# RAFT_DuckLink_UART_Bridge.net
KiCad netlist of a schematic drawn in EAGLE
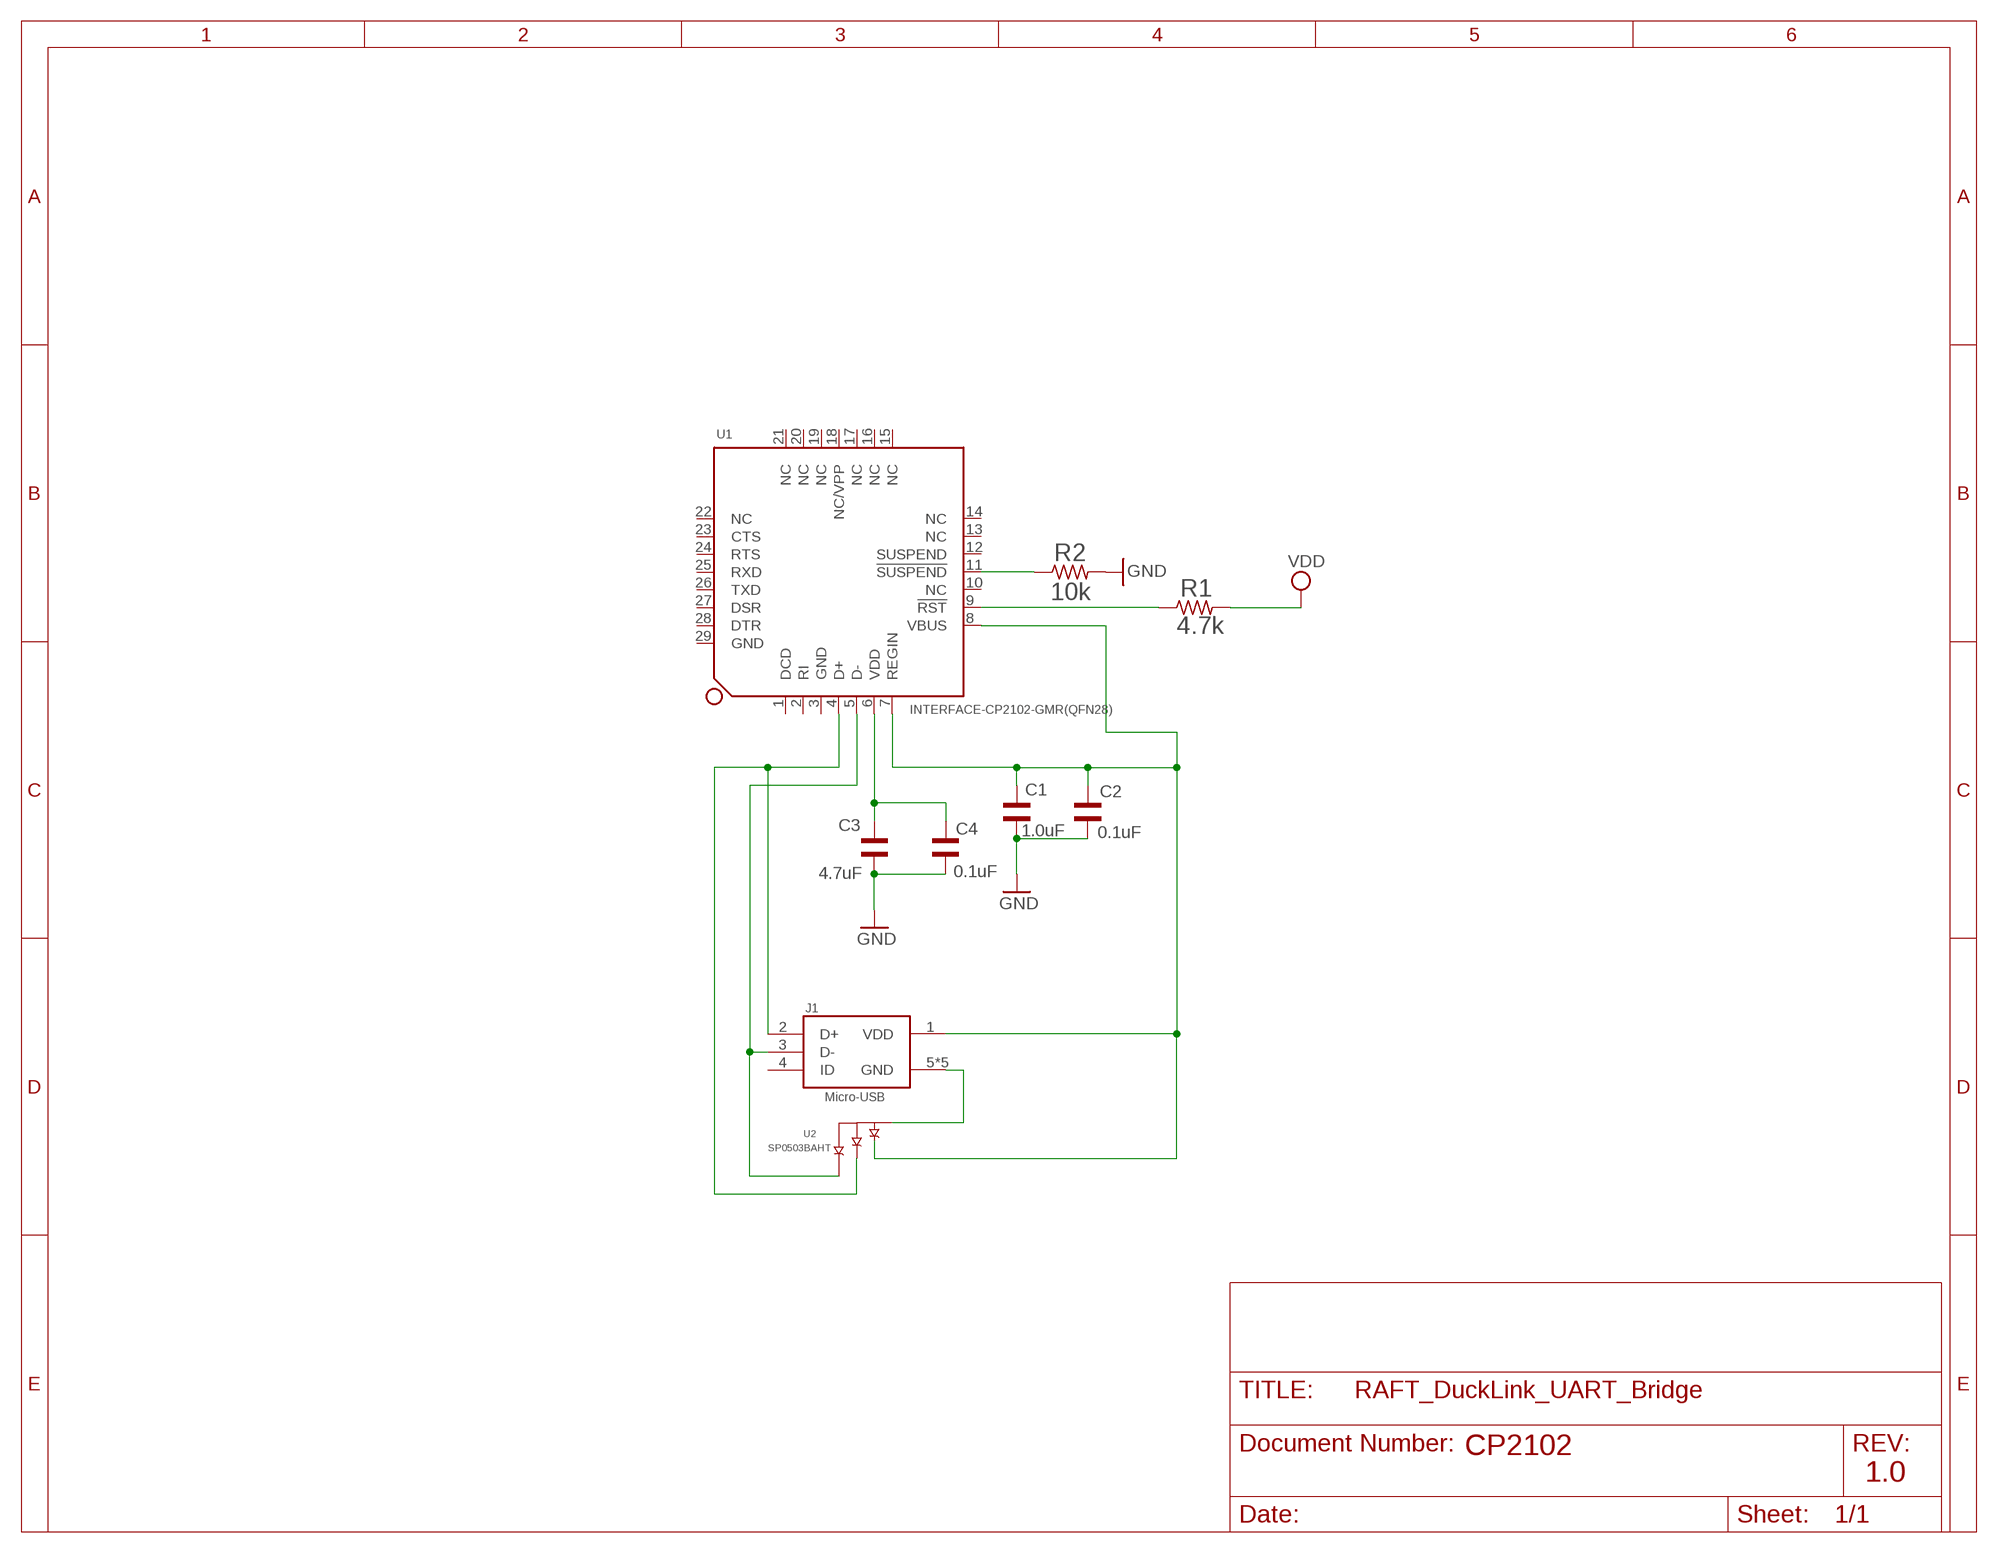
[diagram p0: schematic, sheet 1]

(export (version "E")
  (design (tool "Eeschema 10.0.6"))
  (components
    (comp (ref "C1")
      (value "1.0uF")
      (footprint "eagle-import:CAPC1005X70N")
      (fields (field (name "MF") "Murata") (field (name "MP") "GCM155C71A105KE38D"))
      (libsource (lib "eagle-import") (part "GCM155C71A105KE38D"))
    )
    (comp (ref "C2")
      (value "0.1uF")
      (footprint "eagle-import:CAPC1005X55N")
      (fields (field (name "MF") "Murata") (field (name "MP") "GRM155R71C104KA88D"))
      (libsource (lib "eagle-import") (part "GRM155R71C104KA88D"))
    )
    (comp (ref "C3")
      (value "4.7uF")
      (footprint "eagle-import:CAPC1005X55N")
      (fields (field (name "MF") "Murata") (field (name "MP") "GRM155R60J475ME87D"))
      (libsource (lib "eagle-import") (part "GRM155R60J475ME87D"))
    )
    (comp (ref "C4")
      (value "0.1uF")
      (footprint "eagle-import:CAPC1005X55N")
      (fields (field (name "MF") "Murata") (field (name "MP") "GRM155R71C104KA88D"))
      (libsource (lib "eagle-import") (part "GRM155R71C104KA88D"))
    )
    (comp (ref "J1")
      (value "Micro-USB")
      (footprint "eagle-import:MOLEX_105017-0001")
      (fields
        (field (name "DIGI-KEY_PART_NUMBER") "WM1399CT-ND")
        (field (name "MF") "Molex")
        (field (name "MP") "1050170001")
      )
      (libsource (lib "eagle-import") (part "105017-0001FIXED"))
    )
    (comp (ref "R1")
      (value "4.7k")
      (footprint "eagle-import:RESC1005X35N")
      (fields
        (field (name "DIGI-KEY_PART_NUMBER") "541-3974-1-ND")
        (field (name "MF") "Vishay")
        (field (name "MP") "CRCW04024K70JNEDC")
      )
      (libsource (lib "eagle-import") (part "CRCW04024K70JNEDC"))
    )
    (comp (ref "R2")
      (value "10k")
      (footprint "eagle-import:RESC1005X40N")
      (fields
        (field (name "DIGI-KEY_PART_NUMBER") "541-10KJCT-ND")
        (field (name "MF") "Vishay Dale")
        (field (name "MP") "CRCW040210K0JNED")
      )
      (libsource (lib "eagle-import") (part "CRCW040210K0JNED"))
    )
    (comp (ref "U1")
      (value "INTERFACE-CP2102-GMR(QFN28)")
      (footprint "eagle-import:QFN28G_0.5-5X5MM")
      (fields (field (name "MF") "Silicon") (field (name "MP") "CP2102-GMR"))
      (libsource (lib "eagle-import") (part "INTERFACE-CP2102-GMR(QFN28)"))
    )
    (comp (ref "U2")
      (value "SP0503BAHT")
      (footprint "eagle-import:SOT143")
      (fields (field (name "DIGI-KEY_PART_NUMBER") "SP0503BAHT-ND") (field (name "MF") "Littelfuse Inc."))
      (libsource (lib "eagle-import") (part "SP0503BAHT"))
    )
  )
  (nets
    (net (code "1") (name "GND") (class "Default")
      (node (ref "C1") (pin "1") (pinfunction "1_1") (pintype "passive"))
      (node (ref "C2") (pin "1") (pinfunction "1_1") (pintype "passive"))
      (node (ref "C3") (pin "1") (pinfunction "1_1") (pintype "passive"))
      (node (ref "C4") (pin "1") (pinfunction "1_1") (pintype "passive"))
      (node (ref "R2") (pin "2") (pinfunction "2_2") (pintype "passive"))
    )
    (net (code "2") (name "Net-(J1-D+)") (class "Default")
      (node (ref "J1") (pin "2") (pinfunction "D+_2") (pintype "bidirectional"))
      (node (ref "U1") (pin "4") (pinfunction "D+_4") (pintype "bidirectional"))
      (node (ref "U2") (pin "3") (pinfunction "B_3") (pintype "bidirectional"))
    )
    (net (code "3") (name "Net-(J1-D-)") (class "Default")
      (node (ref "J1") (pin "3") (pinfunction "D-_3") (pintype "bidirectional"))
      (node (ref "U1") (pin "5") (pinfunction "D-_5") (pintype "bidirectional"))
      (node (ref "U2") (pin "4") (pinfunction "C_4") (pintype "bidirectional"))
    )
    (net (code "4") (name "Net-(J1-VDD)") (class "Default")
      (node (ref "C1") (pin "2") (pinfunction "2_2") (pintype "passive"))
      (node (ref "C2") (pin "2") (pinfunction "2_2") (pintype "passive"))
      (node (ref "J1") (pin "1") (pinfunction "VDD_1") (pintype "power_in"))
      (node (ref "U1") (pin "7") (pinfunction "REGIN_7") (pintype "bidirectional"))
      (node (ref "U1") (pin "8") (pinfunction "VBUS_8") (pintype "bidirectional"))
      (node (ref "U2") (pin "2") (pinfunction "A_2") (pintype "bidirectional"))
    )
    (net (code "5") (name "Net-(U1-VDD)") (class "Default")
      (node (ref "C3") (pin "2") (pinfunction "2_2") (pintype "passive"))
      (node (ref "C4") (pin "2") (pinfunction "2_2") (pintype "passive"))
      (node (ref "U1") (pin "6") (pinfunction "VDD_6") (pintype "bidirectional"))
    )
    (net (code "6") (name "Net-(U1-~{RST})") (class "Default")
      (node (ref "R1") (pin "1") (pinfunction "1_1") (pintype "passive"))
      (node (ref "U1") (pin "9") (pinfunction "~{RST}_9") (pintype "bidirectional"))
    )
    (net (code "7") (name "Net-(U1-~{SUSPEND})") (class "Default")
      (node (ref "R2") (pin "1") (pinfunction "1_1") (pintype "passive"))
      (node (ref "U1") (pin "11") (pinfunction "~{SUSPEND}_11") (pintype "bidirectional"))
    )
    (net (code "8") (name "Net-(U2-GND)") (class "Default")
      (node (ref "J1") (pin "5") (pinfunction "GND_5") (pintype "power_in"))
      (node (ref "J1") (pin "P$1") (pinfunction "GND_P$1") (pintype "power_in"))
      (node (ref "J1") (pin "P$2") (pinfunction "GND_P$2") (pintype "power_in"))
      (node (ref "J1") (pin "P$8") (pinfunction "GND_P$8") (pintype "power_in"))
      (node (ref "J1") (pin "P$9") (pinfunction "GND_P$9") (pintype "power_in"))
      (node (ref "U2") (pin "1") (pinfunction "GND_1") (pintype "bidirectional"))
    )
    (net (code "9") (name "VDD") (class "Default")
      (node (ref "R1") (pin "2") (pinfunction "2_2") (pintype "passive"))
    )
    (net (code "10") (name "unconnected-(J1-ID-Pad4)") (class "Default")
      (node (ref "J1") (pin "4") (pinfunction "ID_4") (pintype "passive"))
    )
    (net (code "11") (name "unconnected-(U1-CTS-Pad23)") (class "Default")
      (node (ref "U1") (pin "23") (pinfunction "CTS_23") (pintype "bidirectional"))
    )
    (net (code "12") (name "unconnected-(U1-DCD-Pad1)") (class "Default")
      (node (ref "U1") (pin "1") (pinfunction "DCD_1") (pintype "bidirectional"))
    )
    (net (code "13") (name "unconnected-(U1-DSR-Pad27)") (class "Default")
      (node (ref "U1") (pin "27") (pinfunction "DSR_27") (pintype "bidirectional"))
    )
    (net (code "14") (name "unconnected-(U1-DTR-Pad28)") (class "Default")
      (node (ref "U1") (pin "28") (pinfunction "DTR_28") (pintype "bidirectional"))
    )
    (net (code "15") (name "unconnected-(U1-GND-Pad3)") (class "Default")
      (node (ref "U1") (pin "3") (pinfunction "GND_3") (pintype "bidirectional"))
    )
    (net (code "16") (name "unconnected-(U1-GND-Pad29)") (class "Default")
      (node (ref "U1") (pin "29") (pinfunction "GND_29") (pintype "bidirectional"))
    )
    (net (code "17") (name "unconnected-(U1-NC-Pad10)") (class "Default")
      (node (ref "U1") (pin "10") (pinfunction "NC_10") (pintype "bidirectional"))
    )
    (net (code "18") (name "unconnected-(U1-NC-Pad13)") (class "Default")
      (node (ref "U1") (pin "13") (pinfunction "NC_13") (pintype "bidirectional"))
    )
    (net (code "19") (name "unconnected-(U1-NC-Pad14)") (class "Default")
      (node (ref "U1") (pin "14") (pinfunction "NC_14") (pintype "bidirectional"))
    )
    (net (code "20") (name "unconnected-(U1-NC-Pad15)") (class "Default")
      (node (ref "U1") (pin "15") (pinfunction "NC_15") (pintype "bidirectional"))
    )
    (net (code "21") (name "unconnected-(U1-NC-Pad16)") (class "Default")
      (node (ref "U1") (pin "16") (pinfunction "NC_16") (pintype "bidirectional"))
    )
    (net (code "22") (name "unconnected-(U1-NC-Pad17)") (class "Default")
      (node (ref "U1") (pin "17") (pinfunction "NC_17") (pintype "bidirectional"))
    )
    (net (code "23") (name "unconnected-(U1-NC-Pad19)") (class "Default")
      (node (ref "U1") (pin "19") (pinfunction "NC_19") (pintype "bidirectional"))
    )
    (net (code "24") (name "unconnected-(U1-NC-Pad20)") (class "Default")
      (node (ref "U1") (pin "20") (pinfunction "NC_20") (pintype "bidirectional"))
    )
    (net (code "25") (name "unconnected-(U1-NC-Pad21)") (class "Default")
      (node (ref "U1") (pin "21") (pinfunction "NC_21") (pintype "bidirectional"))
    )
    (net (code "26") (name "unconnected-(U1-NC-Pad22)") (class "Default")
      (node (ref "U1") (pin "22") (pinfunction "NC_22") (pintype "bidirectional"))
    )
    (net (code "27") (name "unconnected-(U1-NC{slash}VPP-Pad18)") (class "Default")
      (node (ref "U1") (pin "18") (pinfunction "NC/VPP_18") (pintype "bidirectional"))
    )
    (net (code "28") (name "unconnected-(U1-RI-Pad2)") (class "Default")
      (node (ref "U1") (pin "2") (pinfunction "RI_2") (pintype "bidirectional"))
    )
    (net (code "29") (name "unconnected-(U1-RTS-Pad24)") (class "Default")
      (node (ref "U1") (pin "24") (pinfunction "RTS_24") (pintype "bidirectional"))
    )
    (net (code "30") (name "unconnected-(U1-RXD-Pad25)") (class "Default")
      (node (ref "U1") (pin "25") (pinfunction "RXD_25") (pintype "bidirectional"))
    )
    (net (code "31") (name "unconnected-(U1-SUSPEND-Pad12)") (class "Default")
      (node (ref "U1") (pin "12") (pinfunction "SUSPEND_12") (pintype "bidirectional"))
    )
    (net (code "32") (name "unconnected-(U1-TXD-Pad26)") (class "Default")
      (node (ref "U1") (pin "26") (pinfunction "TXD_26") (pintype "bidirectional"))
    )
  )
)
